# dc_mini_fan_controller.net
KiCad netlist of a schematic drawn in Altium Designer
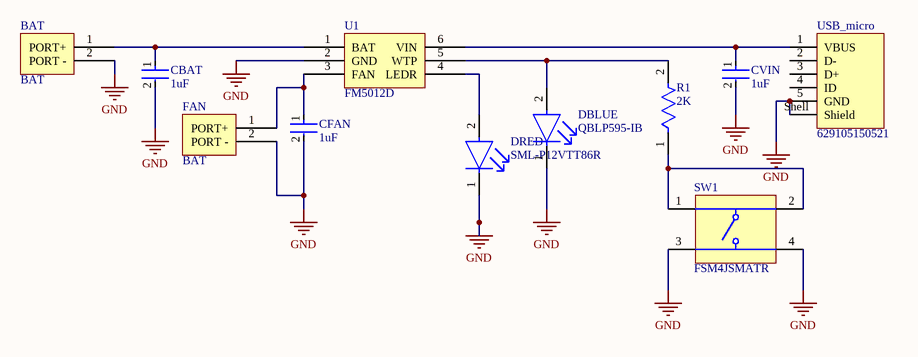
[diagram p0: dc_mini_fan_controller.SchDoc]

(export (version "E")
  (design (tool "Eeschema 10.0.6"))
  (components
    (comp (ref "BAT") (value "BAT") (footprint "BAT") (libsource (lib "dc_mini_fan_controller") (part "BAT")))
    (comp (ref "CBAT")
      (value "1uF")
      (footprint "FP-GRM15-0_1-MFG")
      (description "CAP CER 1UF 10V X5R 0402")
      (fields
        (field (name "OCTOPART") "https://octopart.com/grm155r61a105ke15d-murata-197442")
        (field (name "MANUFACTURER PART NUMBER") "GRM155R61A105KE15D")
      )
      (libsource (lib "Altium Content Vault") (part "02cd4be3c70576c341d710602a673aa"))
    )
    (comp (ref "CFAN")
      (value "1uF")
      (footprint "FP-GRM15-0_1-MFG")
      (description "CAP CER 1UF 10V X5R 0402")
      (fields
        (field (name "OCTOPART") "https://octopart.com/grm155r61a105ke15d-murata-197442")
        (field (name "MANUFACTURER PART NUMBER") "GRM155R61A105KE15D")
      )
      (libsource (lib "Altium Content Vault") (part "02cd4be3c70576c341d710602a673aa"))
    )
    (comp (ref "CVIN")
      (value "1uF")
      (footprint "FP-GRM15-0_1-MFG")
      (description "CAP CER 1UF 10V X5R 0402")
      (fields
        (field (name "OCTOPART") "https://octopart.com/grm155r61a105ke15d-murata-197442")
        (field (name "MANUFACTURER PART NUMBER") "GRM155R61A105KE15D")
      )
      (libsource (lib "Altium Content Vault") (part "02cd4be3c70576c341d710602a673aa"))
    )
    (comp (ref "DBLUE")
      (value "QBLP595-IB")
      (footprint "FP-QBLP595-IB-MFG")
      (description "LED BLUE CLEAR 0402 SMD")
      (libsource (lib "Altium Content Vault") (part "8706943c75ba83719d021d2fdc84c58"))
    )
    (comp (ref "DRED")
      (value "SML-P12VTT86R")
      (footprint "FP-SML-P1-MFG")
      (description "Red 630nm LED Indication - Discrete 2V 0402 (1006 Metric)")
      (fields (field (name "OCTOPART") "https://octopart.com/sml-p12vtt86r-rohm-34112315"))
      (libsource (lib "Altium Content Vault") (part "8706943c75ba83719d021d2fdc84c58"))
    )
    (comp (ref "FAN") (value "BAT") (footprint "BAT") (libsource (lib "dc_mini_fan_controller") (part "BAT")))
    (comp (ref "R1")
      (value "2K")
      (footprint "FP-ERJ2RK-MFG")
      (description "RES SMD 2K OHM 1% 1/10W 0402")
      (fields (field (name "TOLERANCE") "1%"))
      (libsource (lib "Altium Content Vault") (part "1029c3af85768c4190bb7ad29bc67b5"))
    )
    (comp (ref "SW1")
      (value "FSM4JSMATR")
      (footprint "TECO-FSM4JSMATR_V")
      (description "Micro Miniature Push Button Switch FSM JSM, 50 mA, -35 to 85 degC, 4-Pin SMD, RoHS, Tape and Reel")
      (fields (field (name "MANUFACTURER") "TE Connectivity"))
      (libsource (lib "Altium Content Vault") (part "SW-SPST-4_A"))
    )
    (comp (ref "U1")
      (value "FM5012D")
      (footprint "FM5012D")
      (description "SOT23-6")
      (libsource (lib "dc_mini_fan_controller") (part "FM5012D"))
    )
    (comp (ref "USB_micro")
      (value "629105150521")
      (footprint "629105150521")
      (libsource (lib "Altium Content Vault") (part "Micro USB 2.0_Type B_Receptacle_1 Port"))
    )
  )
  (nets
    (net (code "1") (name "GND") (class "Default")
      (node (ref "BAT") (pin "2") (pinfunction "PORT_-_2") (pintype "passive"))
      (node (ref "CBAT") (pin "2") (pinfunction "2_2") (pintype "passive"))
      (node (ref "CFAN") (pin "2") (pinfunction "2_2") (pintype "passive"))
      (node (ref "CVIN") (pin "2") (pinfunction "2_2") (pintype "passive"))
      (node (ref "DBLUE") (pin "1") (pinfunction "C_1") (pintype "passive"))
      (node (ref "DRED") (pin "1") (pinfunction "C_1") (pintype "passive"))
      (node (ref "FAN") (pin "2") (pinfunction "PORT_-_2") (pintype "passive"))
      (node (ref "SW1") (pin "3") (pinfunction "3_3") (pintype "passive"))
      (node (ref "SW1") (pin "4") (pinfunction "4_4") (pintype "passive"))
      (node (ref "U1") (pin "2") (pinfunction "GND_2") (pintype "passive"))
      (node (ref "USB_micro") (pin "5") (pinfunction "GND_5") (pintype "passive"))
      (node (ref "USB_micro") (pin "Shell") (pinfunction "Shield_Shell") (pintype "passive"))
    )
    (net (code "2") (name "Net-(BAT-PORT+)") (class "Default")
      (node (ref "BAT") (pin "1") (pinfunction "PORT+_1") (pintype "passive"))
      (node (ref "CBAT") (pin "1") (pinfunction "1_1") (pintype "passive"))
      (node (ref "U1") (pin "1") (pinfunction "BAT_1") (pintype "passive"))
    )
    (net (code "3") (name "Net-(DBLUE-A)") (class "Default")
      (node (ref "DBLUE") (pin "2") (pinfunction "A_2") (pintype "passive"))
      (node (ref "R1") (pin "2") (pinfunction "2_2") (pintype "passive"))
      (node (ref "U1") (pin "5") (pinfunction "WTP_5") (pintype "passive"))
    )
    (net (code "4") (name "Net-(DRED-A)") (class "Default")
      (node (ref "DRED") (pin "2") (pinfunction "A_2") (pintype "passive"))
      (node (ref "U1") (pin "4") (pinfunction "LEDR_4") (pintype "passive"))
    )
    (net (code "5") (name "Net-(FAN-PORT+)") (class "Default")
      (node (ref "CFAN") (pin "1") (pinfunction "1_1") (pintype "passive"))
      (node (ref "FAN") (pin "1") (pinfunction "PORT+_1") (pintype "passive"))
      (node (ref "U1") (pin "3") (pinfunction "FAN_3") (pintype "passive"))
    )
    (net (code "6") (name "Net-(R1-Pad1)") (class "Default")
      (node (ref "R1") (pin "1") (pinfunction "1_1") (pintype "passive"))
      (node (ref "SW1") (pin "1") (pinfunction "1_1") (pintype "passive"))
      (node (ref "SW1") (pin "2") (pinfunction "2_2") (pintype "passive"))
    )
    (net (code "7") (name "Net-(U1-VIN)") (class "Default")
      (node (ref "CVIN") (pin "1") (pinfunction "1_1") (pintype "passive"))
      (node (ref "U1") (pin "6") (pinfunction "VIN_6") (pintype "passive"))
      (node (ref "USB_micro") (pin "1") (pinfunction "VBUS_1") (pintype "passive"))
    )
    (net (code "8") (name "unconnected-(USB_micro-D+-Pad3)") (class "Default")
      (node (ref "USB_micro") (pin "3") (pinfunction "D+_3") (pintype "passive"))
    )
    (net (code "9") (name "unconnected-(USB_micro-D--Pad2)") (class "Default")
      (node (ref "USB_micro") (pin "2") (pinfunction "D-_2") (pintype "passive"))
    )
    (net (code "10") (name "unconnected-(USB_micro-ID-Pad4)") (class "Default")
      (node (ref "USB_micro") (pin "4") (pinfunction "ID_4") (pintype "passive"))
    )
  )
)
